# PracticumSchematic.net
KiCad netlist of a schematic drawn in EAGLE
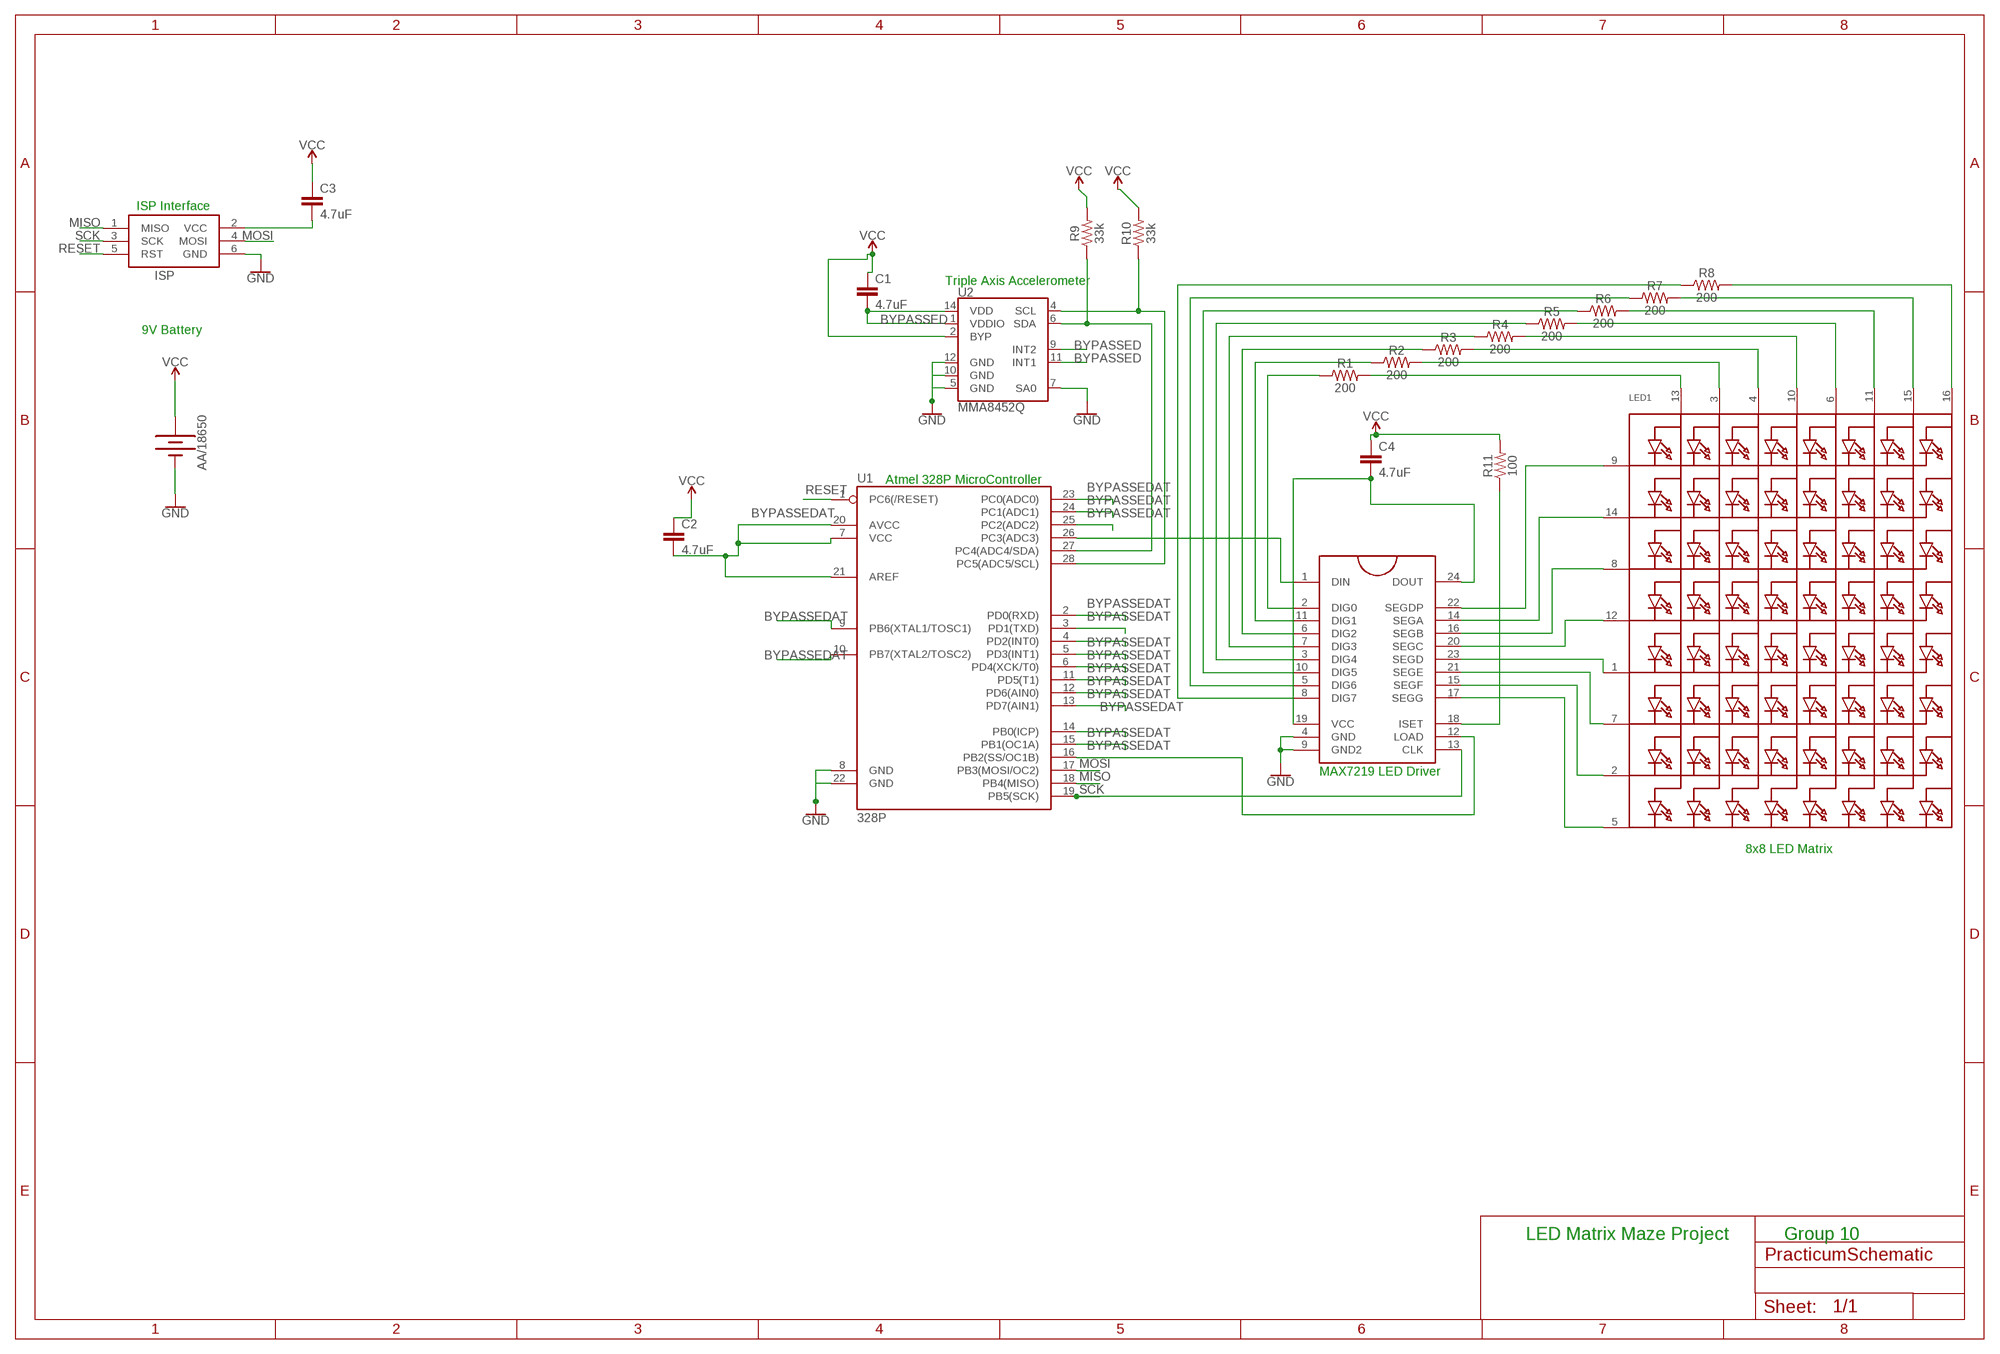
[diagram p0: schematic, sheet 1]

(export (version "E")
  (design (tool "Eeschema 10.0.6"))
  (components
    (comp (ref "AA/18650")
      (value "BATTERY-9V")
      (footprint "eagle-import:BATTCON_9V")
      (libsource (lib "eagle-import") (part "BATTERY-9V"))
    )
    (comp (ref "C1")
      (value "4.7uF")
      (footprint "eagle-import:0603")
      (libsource (lib "eagle-import") (part "4.7UF0603"))
    )
    (comp (ref "C2")
      (value "4.7uF")
      (footprint "eagle-import:0603")
      (libsource (lib "eagle-import") (part "4.7UF0603"))
    )
    (comp (ref "C3")
      (value "4.7uF")
      (footprint "eagle-import:0603")
      (libsource (lib "eagle-import") (part "4.7UF0603"))
    )
    (comp (ref "C4")
      (value "4.7uF")
      (footprint "eagle-import:0603")
      (libsource (lib "eagle-import") (part "4.7UF0603"))
    )
    (comp (ref "ISP")
      (value "AVRISP-6")
      (footprint "eagle-import:AVRISP")
      (libsource (lib "eagle-import") (part "AVRISP-6"))
    )
    (comp (ref "LED1")
      (value "SEGMENT_8X8_ROWCATHODEM12A881UR")
      (footprint "eagle-import:SEGMENT_BL-M12A881UR")
      (libsource (lib "eagle-import") (part "SEGMENT_8X8_ROWCATHODEM12A881UR"))
    )
    (comp (ref "R1")
      (value "200")
      (footprint "eagle-import:0603")
      (libsource (lib "eagle-import") (part "200OHM-0603-1/10W-1%"))
    )
    (comp (ref "R2")
      (value "200")
      (footprint "eagle-import:0603")
      (libsource (lib "eagle-import") (part "200OHM-0603-1/10W-1%"))
    )
    (comp (ref "R3")
      (value "200")
      (footprint "eagle-import:0603")
      (libsource (lib "eagle-import") (part "200OHM-0603-1/10W-1%"))
    )
    (comp (ref "R4")
      (value "200")
      (footprint "eagle-import:0603")
      (libsource (lib "eagle-import") (part "200OHM-0603-1/10W-1%"))
    )
    (comp (ref "R5")
      (value "200")
      (footprint "eagle-import:0603")
      (libsource (lib "eagle-import") (part "200OHM-0603-1/10W-1%"))
    )
    (comp (ref "R6")
      (value "200")
      (footprint "eagle-import:0603")
      (libsource (lib "eagle-import") (part "200OHM-0603-1/10W-1%"))
    )
    (comp (ref "R7")
      (value "200")
      (footprint "eagle-import:0603")
      (libsource (lib "eagle-import") (part "200OHM-0603-1/10W-1%"))
    )
    (comp (ref "R8")
      (value "200")
      (footprint "eagle-import:0603")
      (libsource (lib "eagle-import") (part "200OHM-0603-1/10W-1%"))
    )
    (comp (ref "R9")
      (value "33k")
      (footprint "eagle-import:0603")
      (libsource (lib "eagle-import") (part "33KOHM-0603-1/10W-1%"))
    )
    (comp (ref "R10")
      (value "33k")
      (footprint "eagle-import:0603")
      (libsource (lib "eagle-import") (part "33KOHM-0603-1/10W-1%"))
    )
    (comp (ref "R11")
      (value "100")
      (footprint "eagle-import:0603")
      (libsource (lib "eagle-import") (part "100OHM-0603-1/4W-5%"))
    )
    (comp (ref "U$1")
      (value "MAX7219DIP")
      (footprint "eagle-import:DIL24")
      (libsource (lib "eagle-import") (part "MAX7219DIP"))
    )
    (comp (ref "U1")
      (value "328P")
      (footprint "eagle-import:DIP28")
      (libsource (lib "eagle-import") (part "ATMEGA328P_PDIP"))
    )
    (comp (ref "U2")
      (value "MMA8452Q")
      (footprint "eagle-import:QFN-16")
      (libsource (lib "eagle-import") (part "MMA8452Q"))
    )
  )
  (nets
    (net (code "1") (name "/BYPASSED") (class "Default")
      (node (ref "C1") (pin "2") (pinfunction "2_2") (pintype "passive"))
      (node (ref "U2") (pin "1") (pinfunction "VDDIO_1") (pintype "bidirectional"))
      (node (ref "U2") (pin "11") (pinfunction "INT1_11") (pintype "bidirectional"))
      (node (ref "U2") (pin "14") (pinfunction "VDD_14") (pintype "bidirectional"))
      (node (ref "U2") (pin "9") (pinfunction "INT2_9") (pintype "bidirectional"))
    )
    (net (code "2") (name "/BYPASSEDAT") (class "Default")
      (node (ref "C2") (pin "2") (pinfunction "2_2") (pintype "passive"))
      (node (ref "U1") (pin "10") (pinfunction "PB7(XTAL2/TOSC2)_10") (pintype "bidirectional"))
      (node (ref "U1") (pin "11") (pinfunction "PD5(T1)_11") (pintype "bidirectional"))
      (node (ref "U1") (pin "12") (pinfunction "PD6(AIN0)_12") (pintype "bidirectional"))
      (node (ref "U1") (pin "13") (pinfunction "PD7(AIN1)_13") (pintype "bidirectional"))
      (node (ref "U1") (pin "14") (pinfunction "PB0(ICP)_14") (pintype "bidirectional"))
      (node (ref "U1") (pin "15") (pinfunction "PB1(OC1A)_15") (pintype "bidirectional"))
      (node (ref "U1") (pin "2") (pinfunction "PD0(RXD)_2") (pintype "bidirectional"))
      (node (ref "U1") (pin "20") (pinfunction "AVCC_20") (pintype "bidirectional"))
      (node (ref "U1") (pin "21") (pinfunction "AREF_21") (pintype "bidirectional"))
      (node (ref "U1") (pin "23") (pinfunction "PC0(ADC0)_23") (pintype "bidirectional"))
      (node (ref "U1") (pin "24") (pinfunction "PC1(ADC1)_24") (pintype "bidirectional"))
      (node (ref "U1") (pin "25") (pinfunction "PC2(ADC2)_25") (pintype "bidirectional"))
      (node (ref "U1") (pin "3") (pinfunction "PD1(TXD)_3") (pintype "bidirectional"))
      (node (ref "U1") (pin "4") (pinfunction "PD2(INT0)_4") (pintype "bidirectional"))
      (node (ref "U1") (pin "5") (pinfunction "PD3(INT1)_5") (pintype "bidirectional"))
      (node (ref "U1") (pin "6") (pinfunction "PD4(XCK/T0)_6") (pintype "bidirectional"))
      (node (ref "U1") (pin "7") (pinfunction "VCC_7") (pintype "bidirectional"))
      (node (ref "U1") (pin "9") (pinfunction "PB6(XTAL1/TOSC1)_9") (pintype "bidirectional"))
    )
    (net (code "3") (name "/MISO") (class "Default")
      (node (ref "ISP") (pin "1") (pinfunction "MISO_1") (pintype "input"))
      (node (ref "U1") (pin "18") (pinfunction "PB4(MISO)_18") (pintype "bidirectional"))
    )
    (net (code "4") (name "/MOSI") (class "Default")
      (node (ref "ISP") (pin "4") (pinfunction "MOSI_4") (pintype "output"))
      (node (ref "U1") (pin "17") (pinfunction "PB3(MOSI/OC2)_17") (pintype "bidirectional"))
    )
    (net (code "5") (name "/RESET") (class "Default")
      (node (ref "ISP") (pin "5") (pinfunction "RST_5") (pintype "output"))
      (node (ref "U1") (pin "1") (pinfunction "PC6(/RESET)_1") (pintype "bidirectional"))
    )
    (net (code "6") (name "/SCK") (class "Default")
      (node (ref "ISP") (pin "3") (pinfunction "SCK_3") (pintype "output"))
      (node (ref "U$1") (pin "13") (pinfunction "CLK_13") (pintype "bidirectional"))
      (node (ref "U1") (pin "19") (pinfunction "PB5(SCK)_19") (pintype "bidirectional"))
    )
    (net (code "7") (name "GND") (class "Default")
      (node (ref "AA/18650") (pin "-") (pinfunction "-_-") (pintype "power_in"))
      (node (ref "ISP") (pin "6") (pinfunction "GND_6") (pintype "power_in"))
      (node (ref "U$1") (pin "4") (pinfunction "GND_4") (pintype "bidirectional"))
      (node (ref "U$1") (pin "9") (pinfunction "GND2_9") (pintype "bidirectional"))
      (node (ref "U1") (pin "22") (pinfunction "GND_22") (pintype "bidirectional"))
      (node (ref "U1") (pin "8") (pinfunction "GND_8") (pintype "bidirectional"))
      (node (ref "U2") (pin "10") (pinfunction "GND_10") (pintype "bidirectional"))
      (node (ref "U2") (pin "12") (pinfunction "GND_12") (pintype "bidirectional"))
      (node (ref "U2") (pin "5") (pinfunction "GND_5") (pintype "bidirectional"))
      (node (ref "U2") (pin "7") (pinfunction "SA0_7") (pintype "bidirectional"))
    )
    (net (code "8") (name "Net-(ISP-VCC)") (class "Default")
      (node (ref "C3") (pin "2") (pinfunction "2_2") (pintype "passive"))
      (node (ref "ISP") (pin "2") (pinfunction "VCC_2") (pintype "power_in"))
    )
    (net (code "9") (name "Net-(LED1-A1)") (class "Default")
      (node (ref "LED1") (pin "13") (pinfunction "A1_13") (pintype "bidirectional"))
      (node (ref "R1") (pin "2") (pinfunction "2_2") (pintype "passive"))
    )
    (net (code "10") (name "Net-(LED1-A2)") (class "Default")
      (node (ref "LED1") (pin "3") (pinfunction "A2_3") (pintype "bidirectional"))
      (node (ref "R2") (pin "2") (pinfunction "2_2") (pintype "passive"))
    )
    (net (code "11") (name "Net-(LED1-A3)") (class "Default")
      (node (ref "LED1") (pin "4") (pinfunction "A3_4") (pintype "bidirectional"))
      (node (ref "R3") (pin "2") (pinfunction "2_2") (pintype "passive"))
    )
    (net (code "12") (name "Net-(LED1-A4)") (class "Default")
      (node (ref "LED1") (pin "10") (pinfunction "A4_10") (pintype "bidirectional"))
      (node (ref "R4") (pin "2") (pinfunction "2_2") (pintype "passive"))
    )
    (net (code "13") (name "Net-(LED1-A5)") (class "Default")
      (node (ref "LED1") (pin "6") (pinfunction "A5_6") (pintype "bidirectional"))
      (node (ref "R5") (pin "2") (pinfunction "2_2") (pintype "passive"))
    )
    (net (code "14") (name "Net-(LED1-A6)") (class "Default")
      (node (ref "LED1") (pin "11") (pinfunction "A6_11") (pintype "bidirectional"))
      (node (ref "R6") (pin "2") (pinfunction "2_2") (pintype "passive"))
    )
    (net (code "15") (name "Net-(LED1-A7)") (class "Default")
      (node (ref "LED1") (pin "15") (pinfunction "A7_15") (pintype "bidirectional"))
      (node (ref "R7") (pin "2") (pinfunction "2_2") (pintype "passive"))
    )
    (net (code "16") (name "Net-(LED1-A8)") (class "Default")
      (node (ref "LED1") (pin "16") (pinfunction "A8_16") (pintype "bidirectional"))
      (node (ref "R8") (pin "2") (pinfunction "2_2") (pintype "passive"))
    )
    (net (code "17") (name "Net-(LED1-K1)") (class "Default")
      (node (ref "LED1") (pin "9") (pinfunction "K1_9") (pintype "bidirectional"))
      (node (ref "U$1") (pin "22") (pinfunction "SEGDP_22") (pintype "bidirectional"))
    )
    (net (code "18") (name "Net-(LED1-K2)") (class "Default")
      (node (ref "LED1") (pin "14") (pinfunction "K2_14") (pintype "bidirectional"))
      (node (ref "U$1") (pin "14") (pinfunction "SEGA_14") (pintype "bidirectional"))
    )
    (net (code "19") (name "Net-(LED1-K3)") (class "Default")
      (node (ref "LED1") (pin "8") (pinfunction "K3_8") (pintype "bidirectional"))
      (node (ref "U$1") (pin "16") (pinfunction "SEGB_16") (pintype "bidirectional"))
    )
    (net (code "20") (name "Net-(LED1-K4)") (class "Default")
      (node (ref "LED1") (pin "12") (pinfunction "K4_12") (pintype "bidirectional"))
      (node (ref "U$1") (pin "20") (pinfunction "SEGC_20") (pintype "bidirectional"))
    )
    (net (code "21") (name "Net-(LED1-K5)") (class "Default")
      (node (ref "LED1") (pin "1") (pinfunction "K5_1") (pintype "bidirectional"))
      (node (ref "U$1") (pin "23") (pinfunction "SEGD_23") (pintype "bidirectional"))
    )
    (net (code "22") (name "Net-(LED1-K6)") (class "Default")
      (node (ref "LED1") (pin "7") (pinfunction "K6_7") (pintype "bidirectional"))
      (node (ref "U$1") (pin "21") (pinfunction "SEGE_21") (pintype "bidirectional"))
    )
    (net (code "23") (name "Net-(LED1-K7)") (class "Default")
      (node (ref "LED1") (pin "2") (pinfunction "K7_2") (pintype "bidirectional"))
      (node (ref "U$1") (pin "15") (pinfunction "SEGF_15") (pintype "bidirectional"))
    )
    (net (code "24") (name "Net-(LED1-K8)") (class "Default")
      (node (ref "LED1") (pin "5") (pinfunction "K8_5") (pintype "bidirectional"))
      (node (ref "U$1") (pin "17") (pinfunction "SEGG_17") (pintype "bidirectional"))
    )
    (net (code "25") (name "Net-(U$1-DIG0)") (class "Default")
      (node (ref "R1") (pin "1") (pinfunction "1_1") (pintype "passive"))
      (node (ref "U$1") (pin "2") (pinfunction "DIG0_2") (pintype "bidirectional"))
    )
    (net (code "26") (name "Net-(U$1-DIG1)") (class "Default")
      (node (ref "R2") (pin "1") (pinfunction "1_1") (pintype "passive"))
      (node (ref "U$1") (pin "11") (pinfunction "DIG1_11") (pintype "bidirectional"))
    )
    (net (code "27") (name "Net-(U$1-DIG2)") (class "Default")
      (node (ref "R3") (pin "1") (pinfunction "1_1") (pintype "passive"))
      (node (ref "U$1") (pin "6") (pinfunction "DIG2_6") (pintype "bidirectional"))
    )
    (net (code "28") (name "Net-(U$1-DIG3)") (class "Default")
      (node (ref "R4") (pin "1") (pinfunction "1_1") (pintype "passive"))
      (node (ref "U$1") (pin "7") (pinfunction "DIG3_7") (pintype "bidirectional"))
    )
    (net (code "29") (name "Net-(U$1-DIG4)") (class "Default")
      (node (ref "R5") (pin "1") (pinfunction "1_1") (pintype "passive"))
      (node (ref "U$1") (pin "3") (pinfunction "DIG4_3") (pintype "bidirectional"))
    )
    (net (code "30") (name "Net-(U$1-DIG5)") (class "Default")
      (node (ref "R6") (pin "1") (pinfunction "1_1") (pintype "passive"))
      (node (ref "U$1") (pin "10") (pinfunction "DIG5_10") (pintype "bidirectional"))
    )
    (net (code "31") (name "Net-(U$1-DIG6)") (class "Default")
      (node (ref "R7") (pin "1") (pinfunction "1_1") (pintype "passive"))
      (node (ref "U$1") (pin "5") (pinfunction "DIG6_5") (pintype "bidirectional"))
    )
    (net (code "32") (name "Net-(U$1-DIG7)") (class "Default")
      (node (ref "R8") (pin "1") (pinfunction "1_1") (pintype "passive"))
      (node (ref "U$1") (pin "8") (pinfunction "DIG7_8") (pintype "bidirectional"))
    )
    (net (code "33") (name "Net-(U$1-DIN)") (class "Default")
      (node (ref "U$1") (pin "1") (pinfunction "DIN_1") (pintype "bidirectional"))
      (node (ref "U1") (pin "26") (pinfunction "PC3(ADC3)_26") (pintype "bidirectional"))
    )
    (net (code "34") (name "Net-(U$1-DOUT)") (class "Default")
      (node (ref "C4") (pin "2") (pinfunction "2_2") (pintype "passive"))
      (node (ref "U$1") (pin "19") (pinfunction "VCC_19") (pintype "bidirectional"))
      (node (ref "U$1") (pin "24") (pinfunction "DOUT_24") (pintype "bidirectional"))
    )
    (net (code "35") (name "Net-(U$1-ISET)") (class "Default")
      (node (ref "R11") (pin "1") (pinfunction "1_1") (pintype "passive"))
      (node (ref "U$1") (pin "18") (pinfunction "ISET_18") (pintype "bidirectional"))
    )
    (net (code "36") (name "Net-(U$1-LOAD)") (class "Default")
      (node (ref "U$1") (pin "12") (pinfunction "LOAD_12") (pintype "bidirectional"))
      (node (ref "U1") (pin "16") (pinfunction "PB2(SS/OC1B)_16") (pintype "bidirectional"))
    )
    (net (code "37") (name "Net-(U1-PC4(ADC4{slash}SDA))") (class "Default")
      (node (ref "R9") (pin "1") (pinfunction "1_1") (pintype "passive"))
      (node (ref "U1") (pin "27") (pinfunction "PC4(ADC4/SDA)_27") (pintype "bidirectional"))
      (node (ref "U2") (pin "6") (pinfunction "SDA_6") (pintype "bidirectional"))
    )
    (net (code "38") (name "Net-(U1-PC5(ADC5{slash}SCL))") (class "Default")
      (node (ref "R10") (pin "1") (pinfunction "1_1") (pintype "passive"))
      (node (ref "U1") (pin "28") (pinfunction "PC5(ADC5/SCL)_28") (pintype "bidirectional"))
      (node (ref "U2") (pin "4") (pinfunction "SCL_4") (pintype "bidirectional"))
    )
    (net (code "39") (name "VCC") (class "Default")
      (node (ref "AA/18650") (pin "+") (pinfunction "+_+") (pintype "power_in"))
      (node (ref "C1") (pin "1") (pinfunction "1_1") (pintype "passive"))
      (node (ref "C2") (pin "1") (pinfunction "1_1") (pintype "passive"))
      (node (ref "C3") (pin "1") (pinfunction "1_1") (pintype "passive"))
      (node (ref "C4") (pin "1") (pinfunction "1_1") (pintype "passive"))
      (node (ref "R10") (pin "2") (pinfunction "2_2") (pintype "passive"))
      (node (ref "R11") (pin "2") (pinfunction "2_2") (pintype "passive"))
      (node (ref "R9") (pin "2") (pinfunction "2_2") (pintype "passive"))
      (node (ref "U2") (pin "2") (pinfunction "BYP_2") (pintype "bidirectional"))
    )
  )
)
